# Li_Monitor.net
KiCad netlist of a schematic drawn in Altium Designer
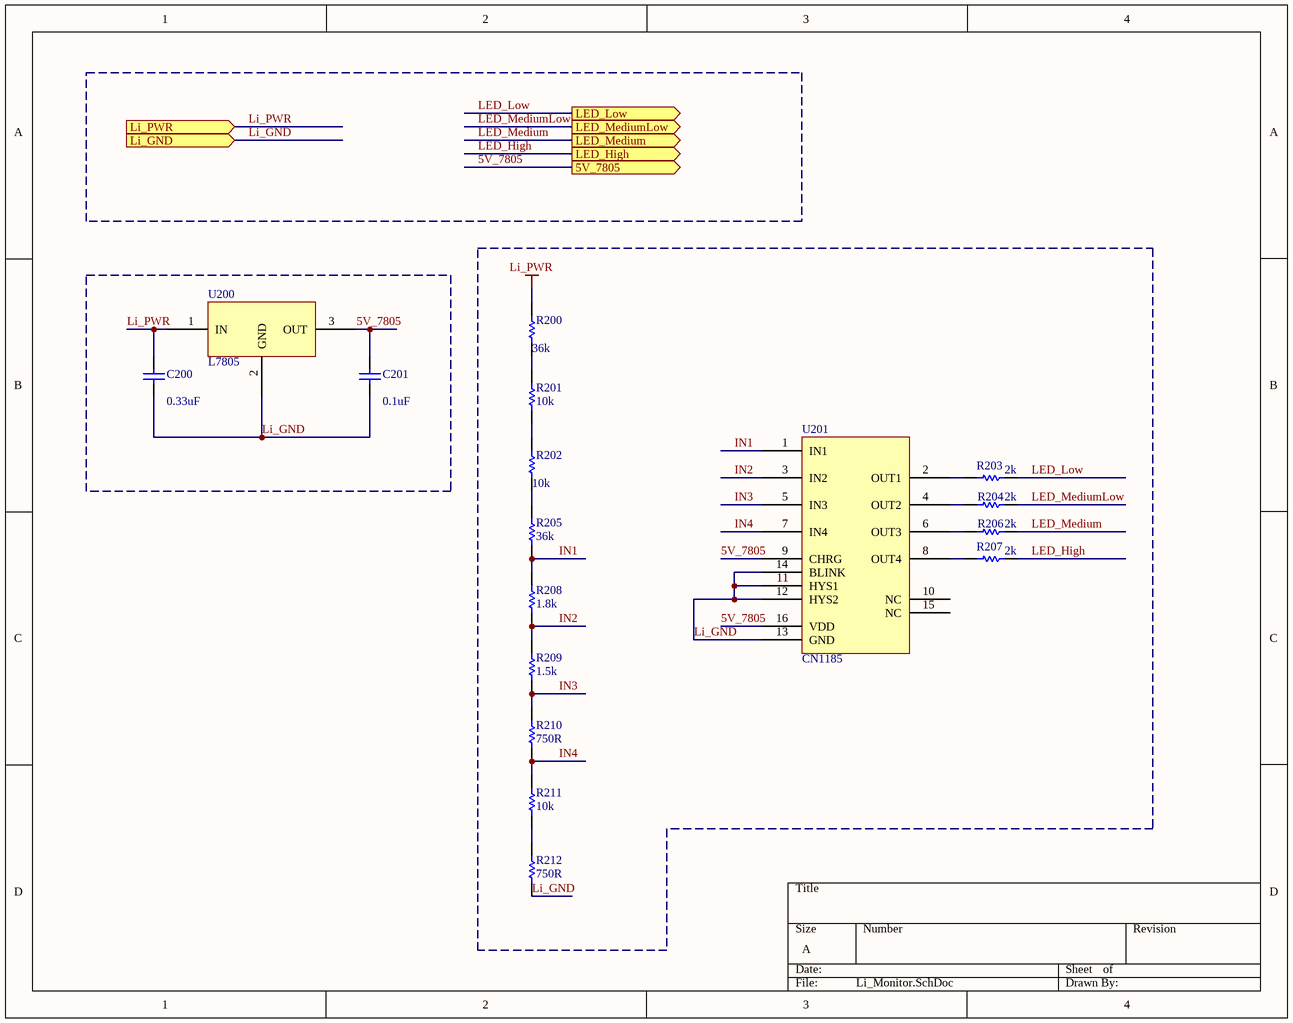
[diagram p0: Li_Monitor.SchDoc]

(export (version "E")
  (design (tool "Eeschema 10.0.6"))
  (components
    (comp (ref "C200")
      (value "0.33uF")
      (footprint "cap0603")
      (description "Capacitor")
      (fields (field (name "PUBLISHER") "Altium Limited"))
      (libsource (lib "Miscellaneous Devices") (part "Cap"))
    )
    (comp (ref "C201")
      (value "0.1uF")
      (footprint "cap0603")
      (description "Capacitor")
      (fields (field (name "PUBLISHER") "Altium Limited"))
      (libsource (lib "Miscellaneous Devices") (part "Cap"))
    )
    (comp (ref "R200")
      (value "36k")
      (footprint "RES0603")
      (description "Resistor")
      (fields (field (name "PUBLISHER") "Altium Limited"))
      (libsource (lib "Miscellaneous Devices") (part "Res1"))
    )
    (comp (ref "R201")
      (value "10k")
      (footprint "RES0603")
      (description "Resistor")
      (fields (field (name "PUBLISHER") "Altium Limited"))
      (libsource (lib "Miscellaneous Devices") (part "Res1"))
    )
    (comp (ref "R202")
      (value "10k")
      (footprint "RES0603")
      (description "Resistor")
      (fields (field (name "PUBLISHER") "Altium Limited"))
      (libsource (lib "Miscellaneous Devices") (part "Res1"))
    )
    (comp (ref "R203")
      (value "2k")
      (footprint "RES0603")
      (description "Resistor")
      (fields (field (name "PUBLISHER") "Altium Limited"))
      (libsource (lib "Miscellaneous Devices") (part "Res1"))
    )
    (comp (ref "R204")
      (value "2k")
      (footprint "RES0603")
      (description "Resistor")
      (fields (field (name "PUBLISHER") "Altium Limited"))
      (libsource (lib "Miscellaneous Devices") (part "Res1"))
    )
    (comp (ref "R205")
      (value "36k")
      (footprint "RES0603")
      (description "Resistor")
      (fields (field (name "PUBLISHER") "Altium Limited"))
      (libsource (lib "Miscellaneous Devices") (part "Res1"))
    )
    (comp (ref "R206")
      (value "2k")
      (footprint "RES0603")
      (description "Resistor")
      (fields (field (name "PUBLISHER") "Altium Limited"))
      (libsource (lib "Miscellaneous Devices") (part "Res1"))
    )
    (comp (ref "R207")
      (value "2k")
      (footprint "RES0603")
      (description "Resistor")
      (fields (field (name "PUBLISHER") "Altium Limited"))
      (libsource (lib "Miscellaneous Devices") (part "Res1"))
    )
    (comp (ref "R208")
      (value "1.8k")
      (footprint "RES0603")
      (description "Resistor")
      (fields (field (name "PUBLISHER") "Altium Limited"))
      (libsource (lib "Miscellaneous Devices") (part "Res1"))
    )
    (comp (ref "R209")
      (value "1.5k")
      (footprint "RES0603")
      (description "Resistor")
      (fields (field (name "PUBLISHER") "Altium Limited"))
      (libsource (lib "Miscellaneous Devices") (part "Res1"))
    )
    (comp (ref "R210")
      (value "750R")
      (footprint "RES0603")
      (description "Resistor")
      (fields (field (name "PUBLISHER") "Altium Limited"))
      (libsource (lib "Miscellaneous Devices") (part "Res1"))
    )
    (comp (ref "R211")
      (value "10k")
      (footprint "RES0603")
      (description "Resistor")
      (fields (field (name "PUBLISHER") "Altium Limited"))
      (libsource (lib "Miscellaneous Devices") (part "Res1"))
    )
    (comp (ref "R212")
      (value "750R")
      (footprint "RES0603")
      (description "Resistor")
      (fields (field (name "PUBLISHER") "Altium Limited"))
      (libsource (lib "Miscellaneous Devices") (part "Res1"))
    )
    (comp (ref "U200")
      (value "L7805")
      (footprint "Miscellaneous Devices:TO-220-AB")
      (libsource (lib "8通道刺激仪") (part "L7805"))
    )
    (comp (ref "U201") (value "CN1185") (footprint "SSOP16_L") (libsource (lib "8通道刺激仪") (part "CN1185")))
  )
  (nets
    (net (code "1") (name "/5V_7805") (class "Default")
      (node (ref "C201") (pin "2") (pinfunction "2_2") (pintype "passive"))
      (node (ref "U200") (pin "3") (pinfunction "OUT_3") (pintype "passive"))
      (node (ref "U201") (pin "16") (pinfunction "VDD_16") (pintype "passive"))
      (node (ref "U201") (pin "9") (pinfunction "CHRG_9") (pintype "passive"))
    )
    (net (code "2") (name "/IN1") (class "Default")
      (node (ref "R205") (pin "1") (pinfunction "1_1") (pintype "passive"))
      (node (ref "R208") (pin "2") (pinfunction "2_2") (pintype "passive"))
      (node (ref "U201") (pin "1") (pinfunction "IN1_1") (pintype "passive"))
    )
    (net (code "3") (name "/IN2") (class "Default")
      (node (ref "R208") (pin "1") (pinfunction "1_1") (pintype "passive"))
      (node (ref "R209") (pin "2") (pinfunction "2_2") (pintype "passive"))
      (node (ref "U201") (pin "3") (pinfunction "IN2_3") (pintype "passive"))
    )
    (net (code "4") (name "/IN3") (class "Default")
      (node (ref "R209") (pin "1") (pinfunction "1_1") (pintype "passive"))
      (node (ref "R210") (pin "2") (pinfunction "2_2") (pintype "passive"))
      (node (ref "U201") (pin "5") (pinfunction "IN3_5") (pintype "passive"))
    )
    (net (code "5") (name "/IN4") (class "Default")
      (node (ref "R210") (pin "1") (pinfunction "1_1") (pintype "passive"))
      (node (ref "R211") (pin "2") (pinfunction "2_2") (pintype "passive"))
      (node (ref "U201") (pin "7") (pinfunction "IN4_7") (pintype "passive"))
    )
    (net (code "6") (name "/LED_High") (class "Default")
      (node (ref "R207") (pin "2") (pinfunction "2_2") (pintype "passive"))
    )
    (net (code "7") (name "/LED_Low") (class "Default")
      (node (ref "R203") (pin "2") (pinfunction "2_2") (pintype "passive"))
    )
    (net (code "8") (name "/LED_Medium") (class "Default")
      (node (ref "R206") (pin "2") (pinfunction "2_2") (pintype "passive"))
    )
    (net (code "9") (name "/LED_MediumLow") (class "Default")
      (node (ref "R204") (pin "2") (pinfunction "2_2") (pintype "passive"))
    )
    (net (code "10") (name "/Li_GND") (class "Default")
      (node (ref "C200") (pin "1") (pinfunction "1_1") (pintype "passive"))
      (node (ref "C201") (pin "1") (pinfunction "1_1") (pintype "passive"))
      (node (ref "R212") (pin "1") (pinfunction "1_1") (pintype "passive"))
      (node (ref "U200") (pin "2") (pinfunction "GND_2") (pintype "passive"))
      (node (ref "U201") (pin "11") (pinfunction "HYS1_11") (pintype "passive"))
      (node (ref "U201") (pin "12") (pinfunction "HYS2_12") (pintype "passive"))
      (node (ref "U201") (pin "13") (pinfunction "GND_13") (pintype "passive"))
      (node (ref "U201") (pin "14") (pinfunction "BLINK_14") (pintype "passive"))
    )
    (net (code "11") (name "Li_PWR") (class "Default")
      (node (ref "C200") (pin "2") (pinfunction "2_2") (pintype "passive"))
      (node (ref "R200") (pin "2") (pinfunction "2_2") (pintype "passive"))
      (node (ref "U200") (pin "1") (pinfunction "IN_1") (pintype "passive"))
    )
    (net (code "12") (name "Net-(R200-Pad1)") (class "Default")
      (node (ref "R200") (pin "1") (pinfunction "1_1") (pintype "passive"))
      (node (ref "R201") (pin "2") (pinfunction "2_2") (pintype "passive"))
    )
    (net (code "13") (name "Net-(R201-Pad1)") (class "Default")
      (node (ref "R201") (pin "1") (pinfunction "1_1") (pintype "passive"))
      (node (ref "R202") (pin "2") (pinfunction "2_2") (pintype "passive"))
    )
    (net (code "14") (name "Net-(R202-Pad1)") (class "Default")
      (node (ref "R202") (pin "1") (pinfunction "1_1") (pintype "passive"))
      (node (ref "R205") (pin "2") (pinfunction "2_2") (pintype "passive"))
    )
    (net (code "15") (name "Net-(R211-Pad1)") (class "Default")
      (node (ref "R211") (pin "1") (pinfunction "1_1") (pintype "passive"))
      (node (ref "R212") (pin "2") (pinfunction "2_2") (pintype "passive"))
    )
    (net (code "16") (name "Net-(U201-OUT1)") (class "Default")
      (node (ref "R203") (pin "1") (pinfunction "1_1") (pintype "passive"))
      (node (ref "U201") (pin "2") (pinfunction "OUT1_2") (pintype "passive"))
    )
    (net (code "17") (name "Net-(U201-OUT2)") (class "Default")
      (node (ref "R204") (pin "1") (pinfunction "1_1") (pintype "passive"))
      (node (ref "U201") (pin "4") (pinfunction "OUT2_4") (pintype "passive"))
    )
    (net (code "18") (name "Net-(U201-OUT3)") (class "Default")
      (node (ref "R206") (pin "1") (pinfunction "1_1") (pintype "passive"))
      (node (ref "U201") (pin "6") (pinfunction "OUT3_6") (pintype "passive"))
    )
    (net (code "19") (name "Net-(U201-OUT4)") (class "Default")
      (node (ref "R207") (pin "1") (pinfunction "1_1") (pintype "passive"))
      (node (ref "U201") (pin "8") (pinfunction "OUT4_8") (pintype "passive"))
    )
    (net (code "20") (name "unconnected-(U201-NC-Pad10)") (class "Default")
      (node (ref "U201") (pin "10") (pinfunction "NC_10") (pintype "passive"))
    )
    (net (code "21") (name "unconnected-(U201-NC-Pad15)") (class "Default")
      (node (ref "U201") (pin "15") (pinfunction "NC_15") (pintype "passive"))
    )
  )
)
